# Micro.net
KiCad netlist of a schematic drawn in Altium Designer
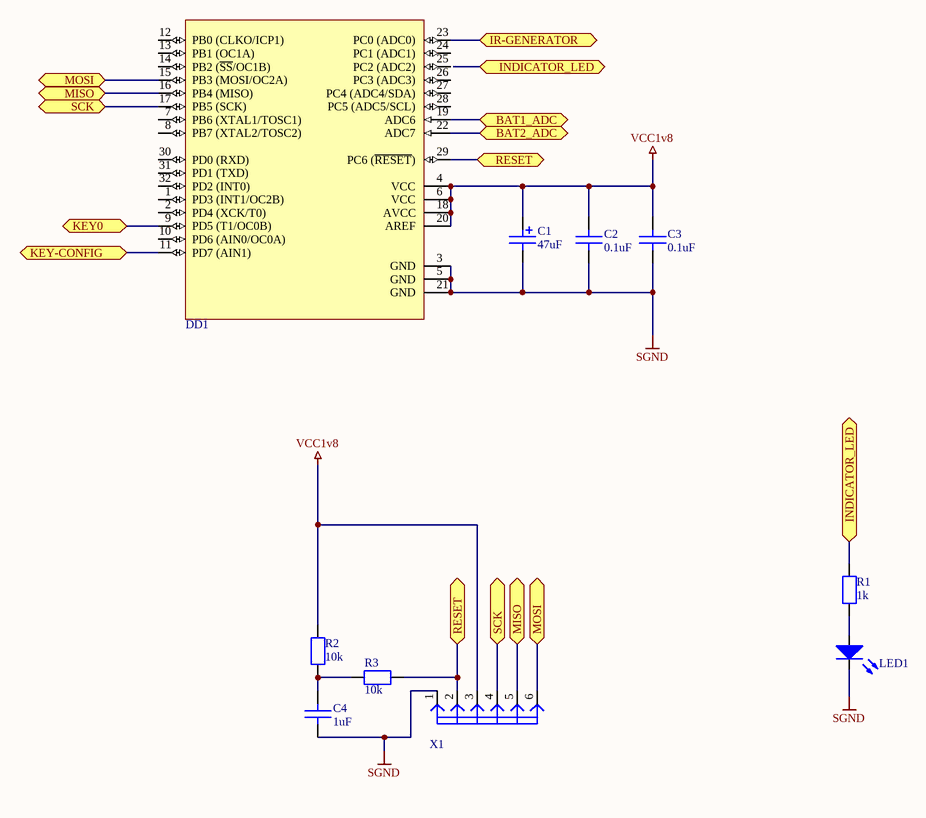
[diagram p0: Micro.SchDoc]

(export (version "E")
  (design (tool "Eeschema 10.0.6"))
  (components
    (comp (ref "C1")
      (value "47uF")
      (footprint "TC2917")
      (description "C47uF-10V-tant")
      (fields (field (name "VOLTAGE") "10V"))
      (libsource (lib "MCounter_Common") (part "C47uF-10V-tant"))
    )
    (comp (ref "C2")
      (value "0.1uF")
      (footprint "C0805")
      (description "C0.1uF-50V")
      (fields (field (name "VOLTAGE") "50V"))
      (libsource (lib "MCounter_Common") (part "C0.1uF-50V"))
    )
    (comp (ref "C3")
      (value "0.1uF")
      (footprint "C0805")
      (description "C0.1uF-50V")
      (fields (field (name "VOLTAGE") "50V"))
      (libsource (lib "MCounter_Common") (part "C0.1uF-50V"))
    )
    (comp (ref "C4")
      (value "1uF")
      (footprint "C0805")
      (description "C1uF-50V")
      (fields (field (name "VOLTAGE") "50V"))
      (libsource (lib "MCounter_Common") (part "C1uF-50V"))
    )
    (comp (ref "DD1")
      (value "ATmega328P")
      (footprint "32A_N")
      (description "8-Bit AVR Microcontroller with 32K Bytes of In-System Programmable Flash Memory")
      (libsource (lib "MCounter_Common") (part "ATmega328P"))
    )
    (comp (ref "LED1")
      (value "LED-RED")
      (footprint "LED-3")
      (description "LED red")
      (libsource (lib "MCounter_Common") (part "LED-RED"))
    )
    (comp (ref "R1")
      (value "1k")
      (footprint "R0805")
      (description "R-1k-5%")
      (fields (field (name "Comment") "R1k-5%"))
      (libsource (lib "MCounter_Common") (part "R1k-5%"))
    )
    (comp (ref "R2")
      (value "10k")
      (footprint "R0805")
      (description "R-10k-5%")
      (fields (field (name "Comment") "R10k-5%"))
      (libsource (lib "") (part "R10k-5%_1"))
    )
    (comp (ref "R3")
      (value "10k")
      (footprint "R0805")
      (description "R-10k-5%")
      (fields (field (name "Comment") "R10k-5%"))
      (libsource (lib "MCounter_Common") (part "R10k-5%"))
    )
    (comp (ref "X1") (value "PLS-6") (footprint "PLS-6") (libsource (lib "MCounter_Common") (part "PLS-6")))
  )
  (nets
    (net (code "1") (name "/BAT1_ADC") (class "Default")
      (node (ref "DD1") (pin "19") (pinfunction "ADC6_19") (pintype "input"))
    )
    (net (code "2") (name "/BAT2_ADC") (class "Default")
      (node (ref "DD1") (pin "22") (pinfunction "ADC7_22") (pintype "input"))
    )
    (net (code "3") (name "/INDICATOR_LED") (class "Default")
      (node (ref "R1") (pin "2") (pinfunction "2_2") (pintype "passive"))
    )
    (net (code "4") (name "/IR-GENERATOR") (class "Default")
      (node (ref "DD1") (pin "23") (pinfunction "PC0_(ADC0)_23") (pintype "bidirectional"))
    )
    (net (code "5") (name "/KEY-CONFIG") (class "Default")
      (node (ref "DD1") (pin "11") (pinfunction "PD7_(AIN1)_11") (pintype "bidirectional"))
    )
    (net (code "6") (name "/KEY0") (class "Default")
      (node (ref "DD1") (pin "9") (pinfunction "PD5_(T1/OC0B)_9") (pintype "bidirectional"))
    )
    (net (code "7") (name "/MISO") (class "Default")
      (node (ref "DD1") (pin "16") (pinfunction "PB4_(MISO)_16") (pintype "bidirectional"))
      (node (ref "X1") (pin "5") (pinfunction "5_5") (pintype "passive"))
    )
    (net (code "8") (name "/MOSI") (class "Default")
      (node (ref "DD1") (pin "15") (pinfunction "PB3_(MOSI/OC2A)_15") (pintype "bidirectional"))
      (node (ref "X1") (pin "6") (pinfunction "6_6") (pintype "passive"))
    )
    (net (code "9") (name "/RESET") (class "Default")
      (node (ref "DD1") (pin "29") (pinfunction "PC6_(~{RESET})_29") (pintype "bidirectional"))
      (node (ref "R3") (pin "2") (pinfunction "2_2") (pintype "passive"))
      (node (ref "X1") (pin "2") (pinfunction "2_2") (pintype "passive"))
    )
    (net (code "10") (name "/SCK") (class "Default")
      (node (ref "DD1") (pin "17") (pinfunction "PB5_(SCK)_17") (pintype "bidirectional"))
      (node (ref "X1") (pin "4") (pinfunction "4_4") (pintype "passive"))
    )
    (net (code "11") (name "Net-(C4-Pad2)") (class "Default")
      (node (ref "C4") (pin "2") (pinfunction "2_2") (pintype "passive"))
      (node (ref "R2") (pin "1") (pinfunction "1_1") (pintype "passive"))
      (node (ref "R3") (pin "1") (pinfunction "1_1") (pintype "passive"))
    )
    (net (code "12") (name "Net-(LED1-A)") (class "Default")
      (node (ref "LED1") (pin "1") (pinfunction "A_1") (pintype "passive"))
      (node (ref "R1") (pin "1") (pinfunction "1_1") (pintype "passive"))
    )
    (net (code "13") (name "SGND") (class "Default")
      (node (ref "C1") (pin "2") (pinfunction "2_2") (pintype "passive"))
      (node (ref "C2") (pin "1") (pinfunction "1_1") (pintype "passive"))
      (node (ref "C3") (pin "1") (pinfunction "1_1") (pintype "passive"))
      (node (ref "C4") (pin "1") (pinfunction "1_1") (pintype "passive"))
      (node (ref "DD1") (pin "21") (pinfunction "GND_21") (pintype "power_in"))
      (node (ref "DD1") (pin "3") (pinfunction "GND_3") (pintype "power_in"))
      (node (ref "DD1") (pin "5") (pinfunction "GND_5") (pintype "power_in"))
      (node (ref "LED1") (pin "2") (pinfunction "K_2") (pintype "passive"))
      (node (ref "X1") (pin "1") (pinfunction "1_1") (pintype "passive"))
    )
    (net (code "14") (name "VCC1v8") (class "Default")
      (node (ref "C1") (pin "1") (pinfunction "1_1") (pintype "passive"))
      (node (ref "C2") (pin "2") (pinfunction "2_2") (pintype "passive"))
      (node (ref "C3") (pin "2") (pinfunction "2_2") (pintype "passive"))
      (node (ref "DD1") (pin "18") (pinfunction "AVCC_18") (pintype "power_in"))
      (node (ref "DD1") (pin "20") (pinfunction "AREF_20") (pintype "passive"))
      (node (ref "DD1") (pin "4") (pinfunction "VCC_4") (pintype "power_in"))
      (node (ref "DD1") (pin "6") (pinfunction "VCC_6") (pintype "power_in"))
      (node (ref "R2") (pin "2") (pinfunction "2_2") (pintype "passive"))
      (node (ref "X1") (pin "3") (pinfunction "3_3") (pintype "passive"))
    )
    (net (code "15") (name "unconnected-(DD1-PB0_(CLKO{slash}ICP1)-Pad12)") (class "Default")
      (node (ref "DD1") (pin "12") (pinfunction "PB0_(CLKO/ICP1)_12") (pintype "bidirectional"))
    )
    (net (code "16") (name "unconnected-(DD1-PB1_(OC1A)-Pad13)") (class "Default")
      (node (ref "DD1") (pin "13") (pinfunction "PB1_(OC1A)_13") (pintype "bidirectional"))
    )
    (net (code "17") (name "unconnected-(DD1-PB2_(~{SS}{slash}OC1B)-Pad14)") (class "Default")
      (node (ref "DD1") (pin "14") (pinfunction "PB2_(~{SS}/OC1B)_14") (pintype "bidirectional"))
    )
    (net (code "18") (name "unconnected-(DD1-PB6_(XTAL1{slash}TOSC1)-Pad7)") (class "Default")
      (node (ref "DD1") (pin "7") (pinfunction "PB6_(XTAL1/TOSC1)_7") (pintype "bidirectional"))
    )
    (net (code "19") (name "unconnected-(DD1-PB7_(XTAL2{slash}TOSC2)-Pad8)") (class "Default")
      (node (ref "DD1") (pin "8") (pinfunction "PB7_(XTAL2/TOSC2)_8") (pintype "bidirectional"))
    )
    (net (code "20") (name "unconnected-(DD1-PC1_(ADC1)-Pad24)") (class "Default")
      (node (ref "DD1") (pin "24") (pinfunction "PC1_(ADC1)_24") (pintype "bidirectional"))
    )
    (net (code "21") (name "unconnected-(DD1-PC2_(ADC2)-Pad25)") (class "Default")
      (node (ref "DD1") (pin "25") (pinfunction "PC2_(ADC2)_25") (pintype "bidirectional"))
    )
    (net (code "22") (name "unconnected-(DD1-PC3_(ADC3)-Pad26)") (class "Default")
      (node (ref "DD1") (pin "26") (pinfunction "PC3_(ADC3)_26") (pintype "bidirectional"))
    )
    (net (code "23") (name "unconnected-(DD1-PC4_(ADC4{slash}SDA)-Pad27)") (class "Default")
      (node (ref "DD1") (pin "27") (pinfunction "PC4_(ADC4/SDA)_27") (pintype "bidirectional"))
    )
    (net (code "24") (name "unconnected-(DD1-PC5_(ADC5{slash}SCL)-Pad28)") (class "Default")
      (node (ref "DD1") (pin "28") (pinfunction "PC5_(ADC5/SCL)_28") (pintype "bidirectional"))
    )
    (net (code "25") (name "unconnected-(DD1-PD0_(RXD)-Pad30)") (class "Default")
      (node (ref "DD1") (pin "30") (pinfunction "PD0_(RXD)_30") (pintype "bidirectional"))
    )
    (net (code "26") (name "unconnected-(DD1-PD1_(TXD)-Pad31)") (class "Default")
      (node (ref "DD1") (pin "31") (pinfunction "PD1_(TXD)_31") (pintype "bidirectional"))
    )
    (net (code "27") (name "unconnected-(DD1-PD2_(INT0)-Pad32)") (class "Default")
      (node (ref "DD1") (pin "32") (pinfunction "PD2_(INT0)_32") (pintype "bidirectional"))
    )
    (net (code "28") (name "unconnected-(DD1-PD3_(INT1{slash}OC2B)-Pad1)") (class "Default")
      (node (ref "DD1") (pin "1") (pinfunction "PD3_(INT1/OC2B)_1") (pintype "bidirectional"))
    )
    (net (code "29") (name "unconnected-(DD1-PD4_(XCK{slash}T0)-Pad2)") (class "Default")
      (node (ref "DD1") (pin "2") (pinfunction "PD4_(XCK/T0)_2") (pintype "bidirectional"))
    )
    (net (code "30") (name "unconnected-(DD1-PD6_(AIN0{slash}OC0A)-Pad10)") (class "Default")
      (node (ref "DD1") (pin "10") (pinfunction "PD6_(AIN0/OC0A)_10") (pintype "bidirectional"))
    )
  )
)
